# buck-regulator.net
KiCad netlist of a schematic drawn in EAGLE
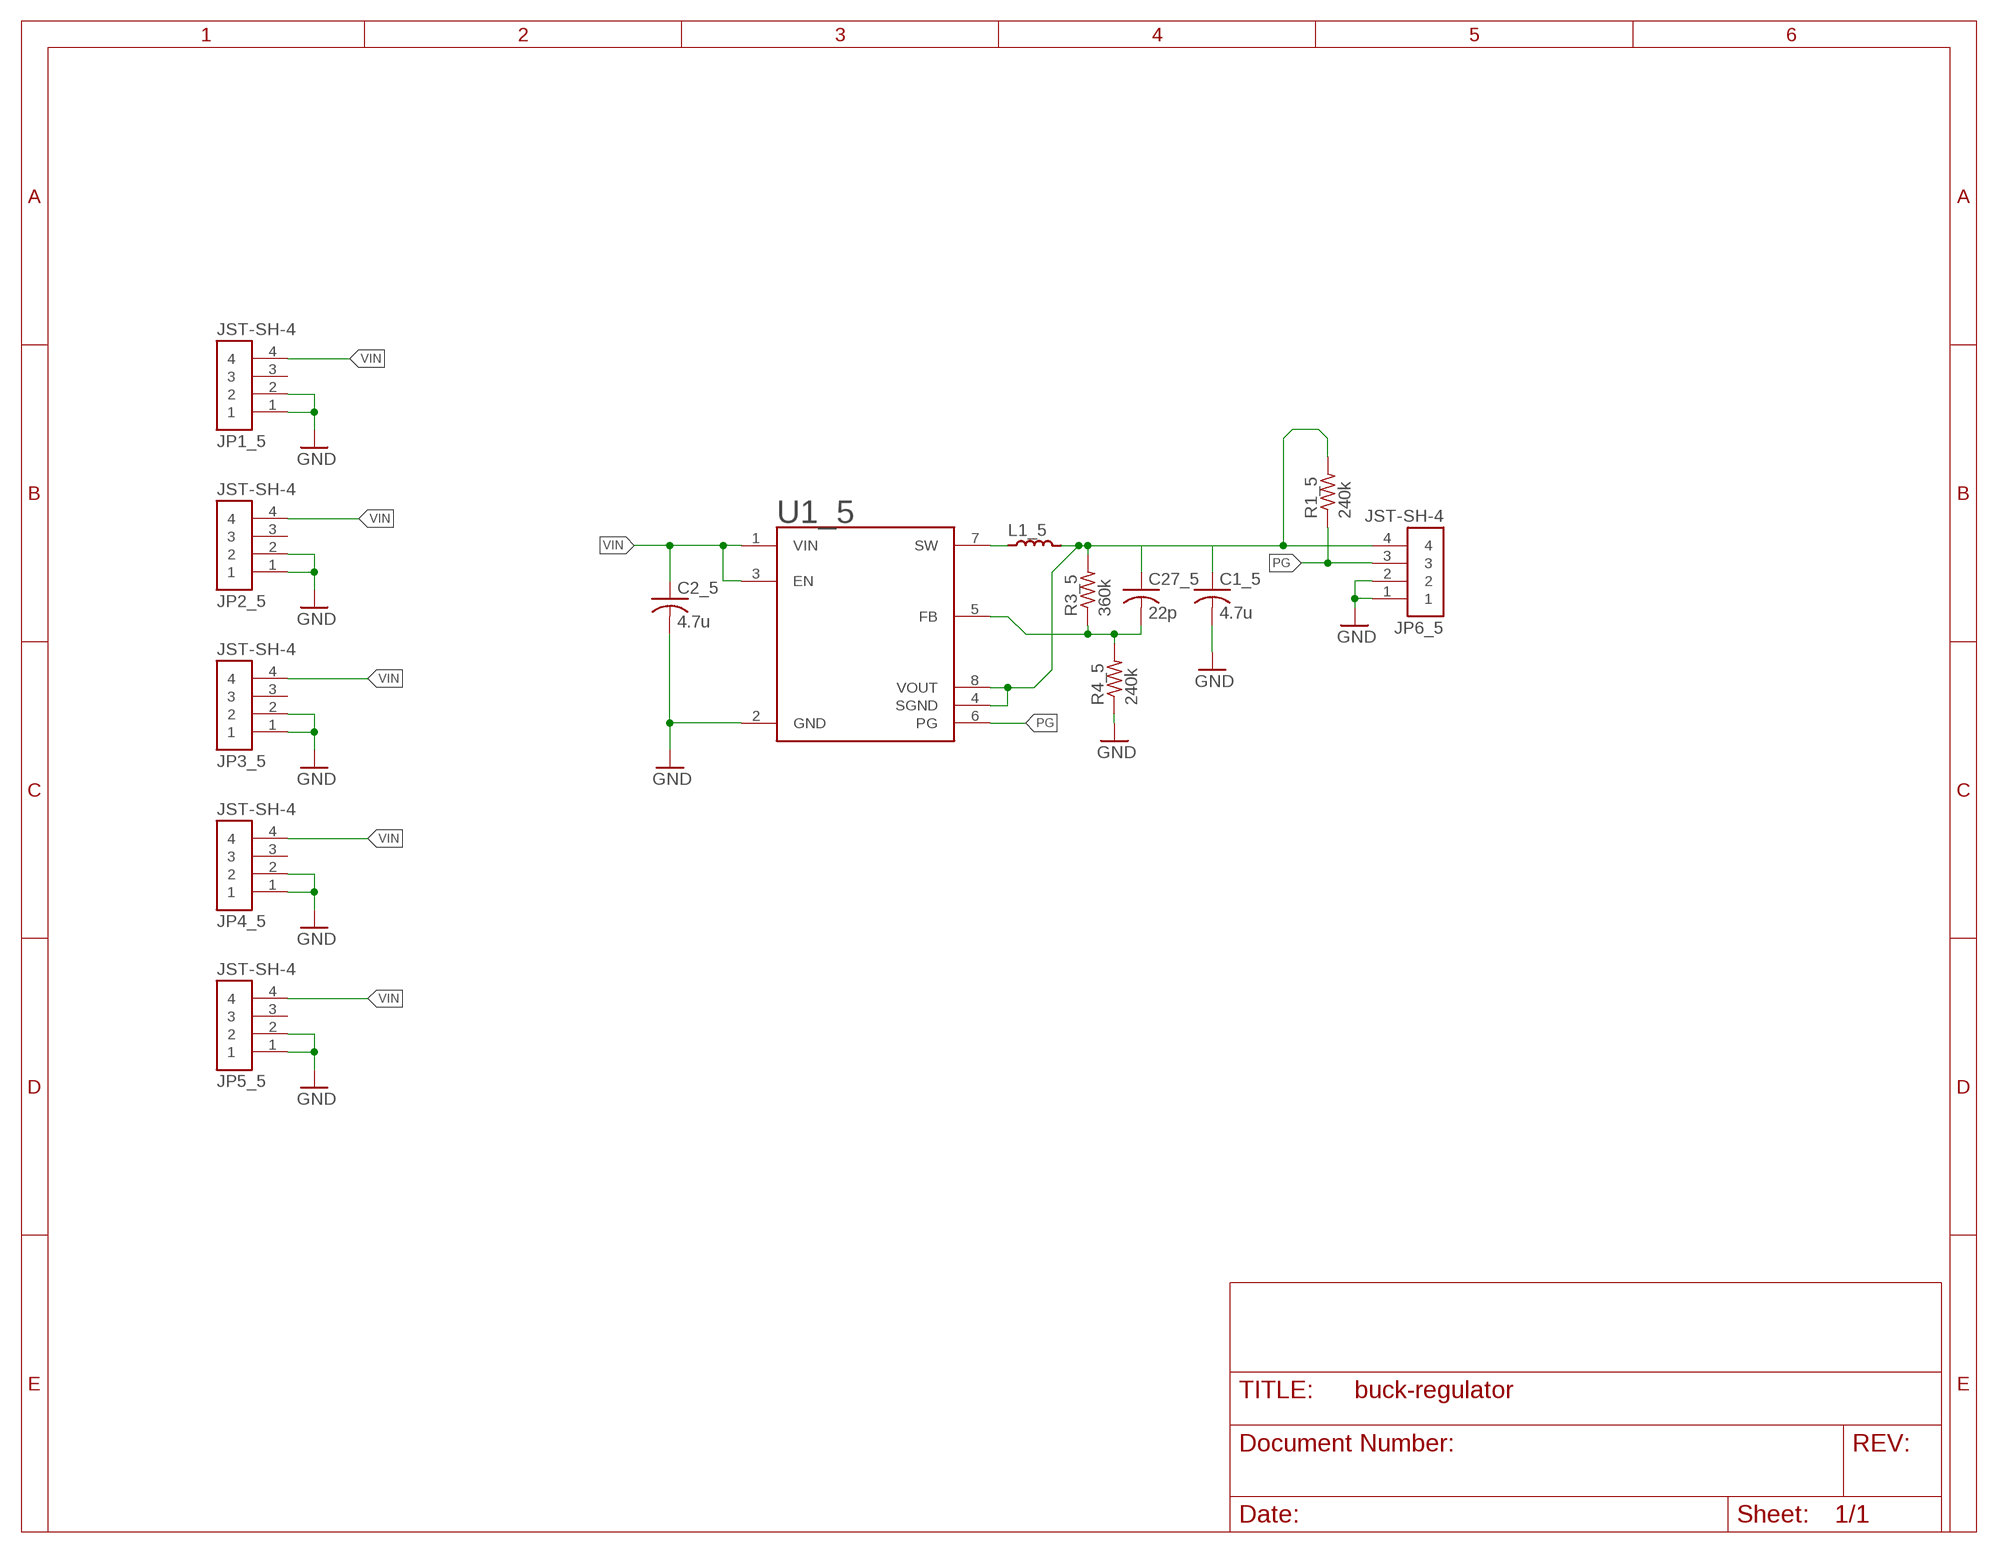
[diagram p0: schematic, sheet 1]

(export (version "E")
  (design (tool "Eeschema 10.0.6"))
  (components
    (comp (ref "C1_5")
      (value "4.7u")
      (footprint "eagle-import:C0603")
      (fields (field (name "MFR") "SAMSUNG"))
      (libsource (lib "eagle-import") (part "C-USC0603"))
    )
    (comp (ref "C2_5")
      (value "4.7u")
      (footprint "eagle-import:C0603")
      (fields (field (name "MFR") "SAMSUNG"))
      (libsource (lib "eagle-import") (part "C-USC0603"))
    )
    (comp (ref "C27_5")
      (value "22p")
      (footprint "eagle-import:C0402")
      (fields (field (name "MFR") "KEMET"))
      (libsource (lib "eagle-import") (part "C-USC0402"))
    )
    (comp (ref "JP1_5")
      (value "JST-SH-4")
      (footprint "eagle-import:JST-SH-4")
      (fields (field (name "MFR") "JST"))
      (libsource (lib "eagle-import") (part "JST-SH-4"))
    )
    (comp (ref "JP2_5")
      (value "JST-SH-4")
      (footprint "eagle-import:JST-SH-4")
      (fields (field (name "MFR") "JST"))
      (libsource (lib "eagle-import") (part "JST-SH-4"))
    )
    (comp (ref "JP3_5")
      (value "JST-SH-4")
      (footprint "eagle-import:JST-SH-4")
      (fields (field (name "MFR") "JST"))
      (libsource (lib "eagle-import") (part "JST-SH-4"))
    )
    (comp (ref "JP4_5")
      (value "JST-SH-4")
      (footprint "eagle-import:JST-SH-4")
      (fields (field (name "MFR") "JST"))
      (libsource (lib "eagle-import") (part "JST-SH-4"))
    )
    (comp (ref "JP5_5")
      (value "JST-SH-4")
      (footprint "eagle-import:JST-SH-4")
      (fields (field (name "MFR") "JST"))
      (libsource (lib "eagle-import") (part "JST-SH-4"))
    )
    (comp (ref "JP6_5")
      (value "JST-SH-4")
      (footprint "eagle-import:JST-SH-4")
      (fields (field (name "MFR") "JST"))
      (libsource (lib "eagle-import") (part "JST-SH-4"))
    )
    (comp (ref "L1_5")
      (value "22u")
      (footprint "eagle-import:LQH3NPNXXXXMEX")
      (fields (field (name "MFR") "MURATA"))
      (libsource (lib "eagle-import") (part "LQH3NPN220MMEL"))
    )
    (comp (ref "R1_5")
      (value "240k")
      (footprint "eagle-import:R0603")
      (fields (field (name "MFR") "PANASONIC"))
      (libsource (lib "eagle-import") (part "R-US_R0603"))
    )
    (comp (ref "R3_5")
      (value "360k")
      (footprint "eagle-import:R0603")
      (fields (field (name "MFR") "PANASONIC"))
      (libsource (lib "eagle-import") (part "R-US_R0603"))
    )
    (comp (ref "R4_5")
      (value "240k")
      (footprint "eagle-import:R0603")
      (fields (field (name "MFR") "PANASONIC"))
      (libsource (lib "eagle-import") (part "R-US_R0603"))
    )
    (comp (ref "U1_5")
      (value "TPS62120")
      (footprint "eagle-import:SOP65P280X145-8N")
      (fields (field (name "MFR") "TI"))
      (libsource (lib "eagle-import") (part "TPS62120"))
    )
  )
  (nets
    (net (code "1") (name "GND") (class "Default")
      (node (ref "C1_5") (pin "2") (pinfunction "2_2") (pintype "passive"))
      (node (ref "C2_5") (pin "2") (pinfunction "2_2") (pintype "passive"))
      (node (ref "JP1_5") (pin "1") (pinfunction "1_1") (pintype "bidirectional"))
      (node (ref "JP1_5") (pin "2") (pinfunction "2_2") (pintype "bidirectional"))
      (node (ref "JP2_5") (pin "1") (pinfunction "1_1") (pintype "bidirectional"))
      (node (ref "JP2_5") (pin "2") (pinfunction "2_2") (pintype "bidirectional"))
      (node (ref "JP3_5") (pin "1") (pinfunction "1_1") (pintype "bidirectional"))
      (node (ref "JP3_5") (pin "2") (pinfunction "2_2") (pintype "bidirectional"))
      (node (ref "JP4_5") (pin "1") (pinfunction "1_1") (pintype "bidirectional"))
      (node (ref "JP4_5") (pin "2") (pinfunction "2_2") (pintype "bidirectional"))
      (node (ref "JP5_5") (pin "1") (pinfunction "1_1") (pintype "bidirectional"))
      (node (ref "JP5_5") (pin "2") (pinfunction "2_2") (pintype "bidirectional"))
      (node (ref "JP6_5") (pin "1") (pinfunction "1_1") (pintype "bidirectional"))
      (node (ref "JP6_5") (pin "2") (pinfunction "2_2") (pintype "bidirectional"))
      (node (ref "R4_5") (pin "1") (pinfunction "1_1") (pintype "passive"))
      (node (ref "U1_5") (pin "2") (pinfunction "GND_2") (pintype "bidirectional"))
    )
    (net (code "2") (name "Net-(U1_5-FB)") (class "Default")
      (node (ref "C27_5") (pin "2") (pinfunction "2_2") (pintype "passive"))
      (node (ref "R3_5") (pin "1") (pinfunction "1_1") (pintype "passive"))
      (node (ref "R4_5") (pin "2") (pinfunction "2_2") (pintype "passive"))
      (node (ref "U1_5") (pin "5") (pinfunction "FB_5") (pintype "bidirectional"))
    )
    (net (code "3") (name "Net-(U1_5-SGND)") (class "Default")
      (node (ref "C1_5") (pin "1") (pinfunction "1_1") (pintype "passive"))
      (node (ref "C27_5") (pin "1") (pinfunction "1_1") (pintype "passive"))
      (node (ref "JP6_5") (pin "4") (pinfunction "4_4") (pintype "bidirectional"))
      (node (ref "L1_5") (pin "P$2") (pinfunction "P$2_P$2") (pintype "bidirectional"))
      (node (ref "R1_5") (pin "2") (pinfunction "2_2") (pintype "passive"))
      (node (ref "R3_5") (pin "2") (pinfunction "2_2") (pintype "passive"))
      (node (ref "U1_5") (pin "4") (pinfunction "SGND_4") (pintype "bidirectional"))
      (node (ref "U1_5") (pin "8") (pinfunction "VOUT_8") (pintype "bidirectional"))
    )
    (net (code "4") (name "Net-(U1_5-SW)") (class "Default")
      (node (ref "L1_5") (pin "P$1") (pinfunction "P$1_P$1") (pintype "bidirectional"))
      (node (ref "U1_5") (pin "7") (pinfunction "SW_7") (pintype "bidirectional"))
    )
    (net (code "5") (name "PG") (class "Default")
      (node (ref "JP6_5") (pin "3") (pinfunction "3_3") (pintype "bidirectional"))
      (node (ref "R1_5") (pin "1") (pinfunction "1_1") (pintype "passive"))
      (node (ref "U1_5") (pin "6") (pinfunction "PG_6") (pintype "bidirectional"))
    )
    (net (code "6") (name "VIN") (class "Default")
      (node (ref "C2_5") (pin "1") (pinfunction "1_1") (pintype "passive"))
      (node (ref "JP1_5") (pin "4") (pinfunction "4_4") (pintype "bidirectional"))
      (node (ref "JP2_5") (pin "4") (pinfunction "4_4") (pintype "bidirectional"))
      (node (ref "JP3_5") (pin "4") (pinfunction "4_4") (pintype "bidirectional"))
      (node (ref "JP4_5") (pin "4") (pinfunction "4_4") (pintype "bidirectional"))
      (node (ref "JP5_5") (pin "4") (pinfunction "4_4") (pintype "bidirectional"))
      (node (ref "U1_5") (pin "1") (pinfunction "VIN_1") (pintype "bidirectional"))
      (node (ref "U1_5") (pin "3") (pinfunction "EN_3") (pintype "bidirectional"))
    )
    (net (code "7") (name "unconnected-(JP1_5-Pad3)") (class "Default")
      (node (ref "JP1_5") (pin "3") (pinfunction "3_3") (pintype "bidirectional"))
    )
    (net (code "8") (name "unconnected-(JP2_5-Pad3)") (class "Default")
      (node (ref "JP2_5") (pin "3") (pinfunction "3_3") (pintype "bidirectional"))
    )
    (net (code "9") (name "unconnected-(JP3_5-Pad3)") (class "Default")
      (node (ref "JP3_5") (pin "3") (pinfunction "3_3") (pintype "bidirectional"))
    )
    (net (code "10") (name "unconnected-(JP4_5-Pad3)") (class "Default")
      (node (ref "JP4_5") (pin "3") (pinfunction "3_3") (pintype "bidirectional"))
    )
    (net (code "11") (name "unconnected-(JP5_5-Pad3)") (class "Default")
      (node (ref "JP5_5") (pin "3") (pinfunction "3_3") (pintype "bidirectional"))
    )
  )
)
